# Moter_Control_2021-08-13.net
KiCad netlist of a schematic drawn in Altium Designer
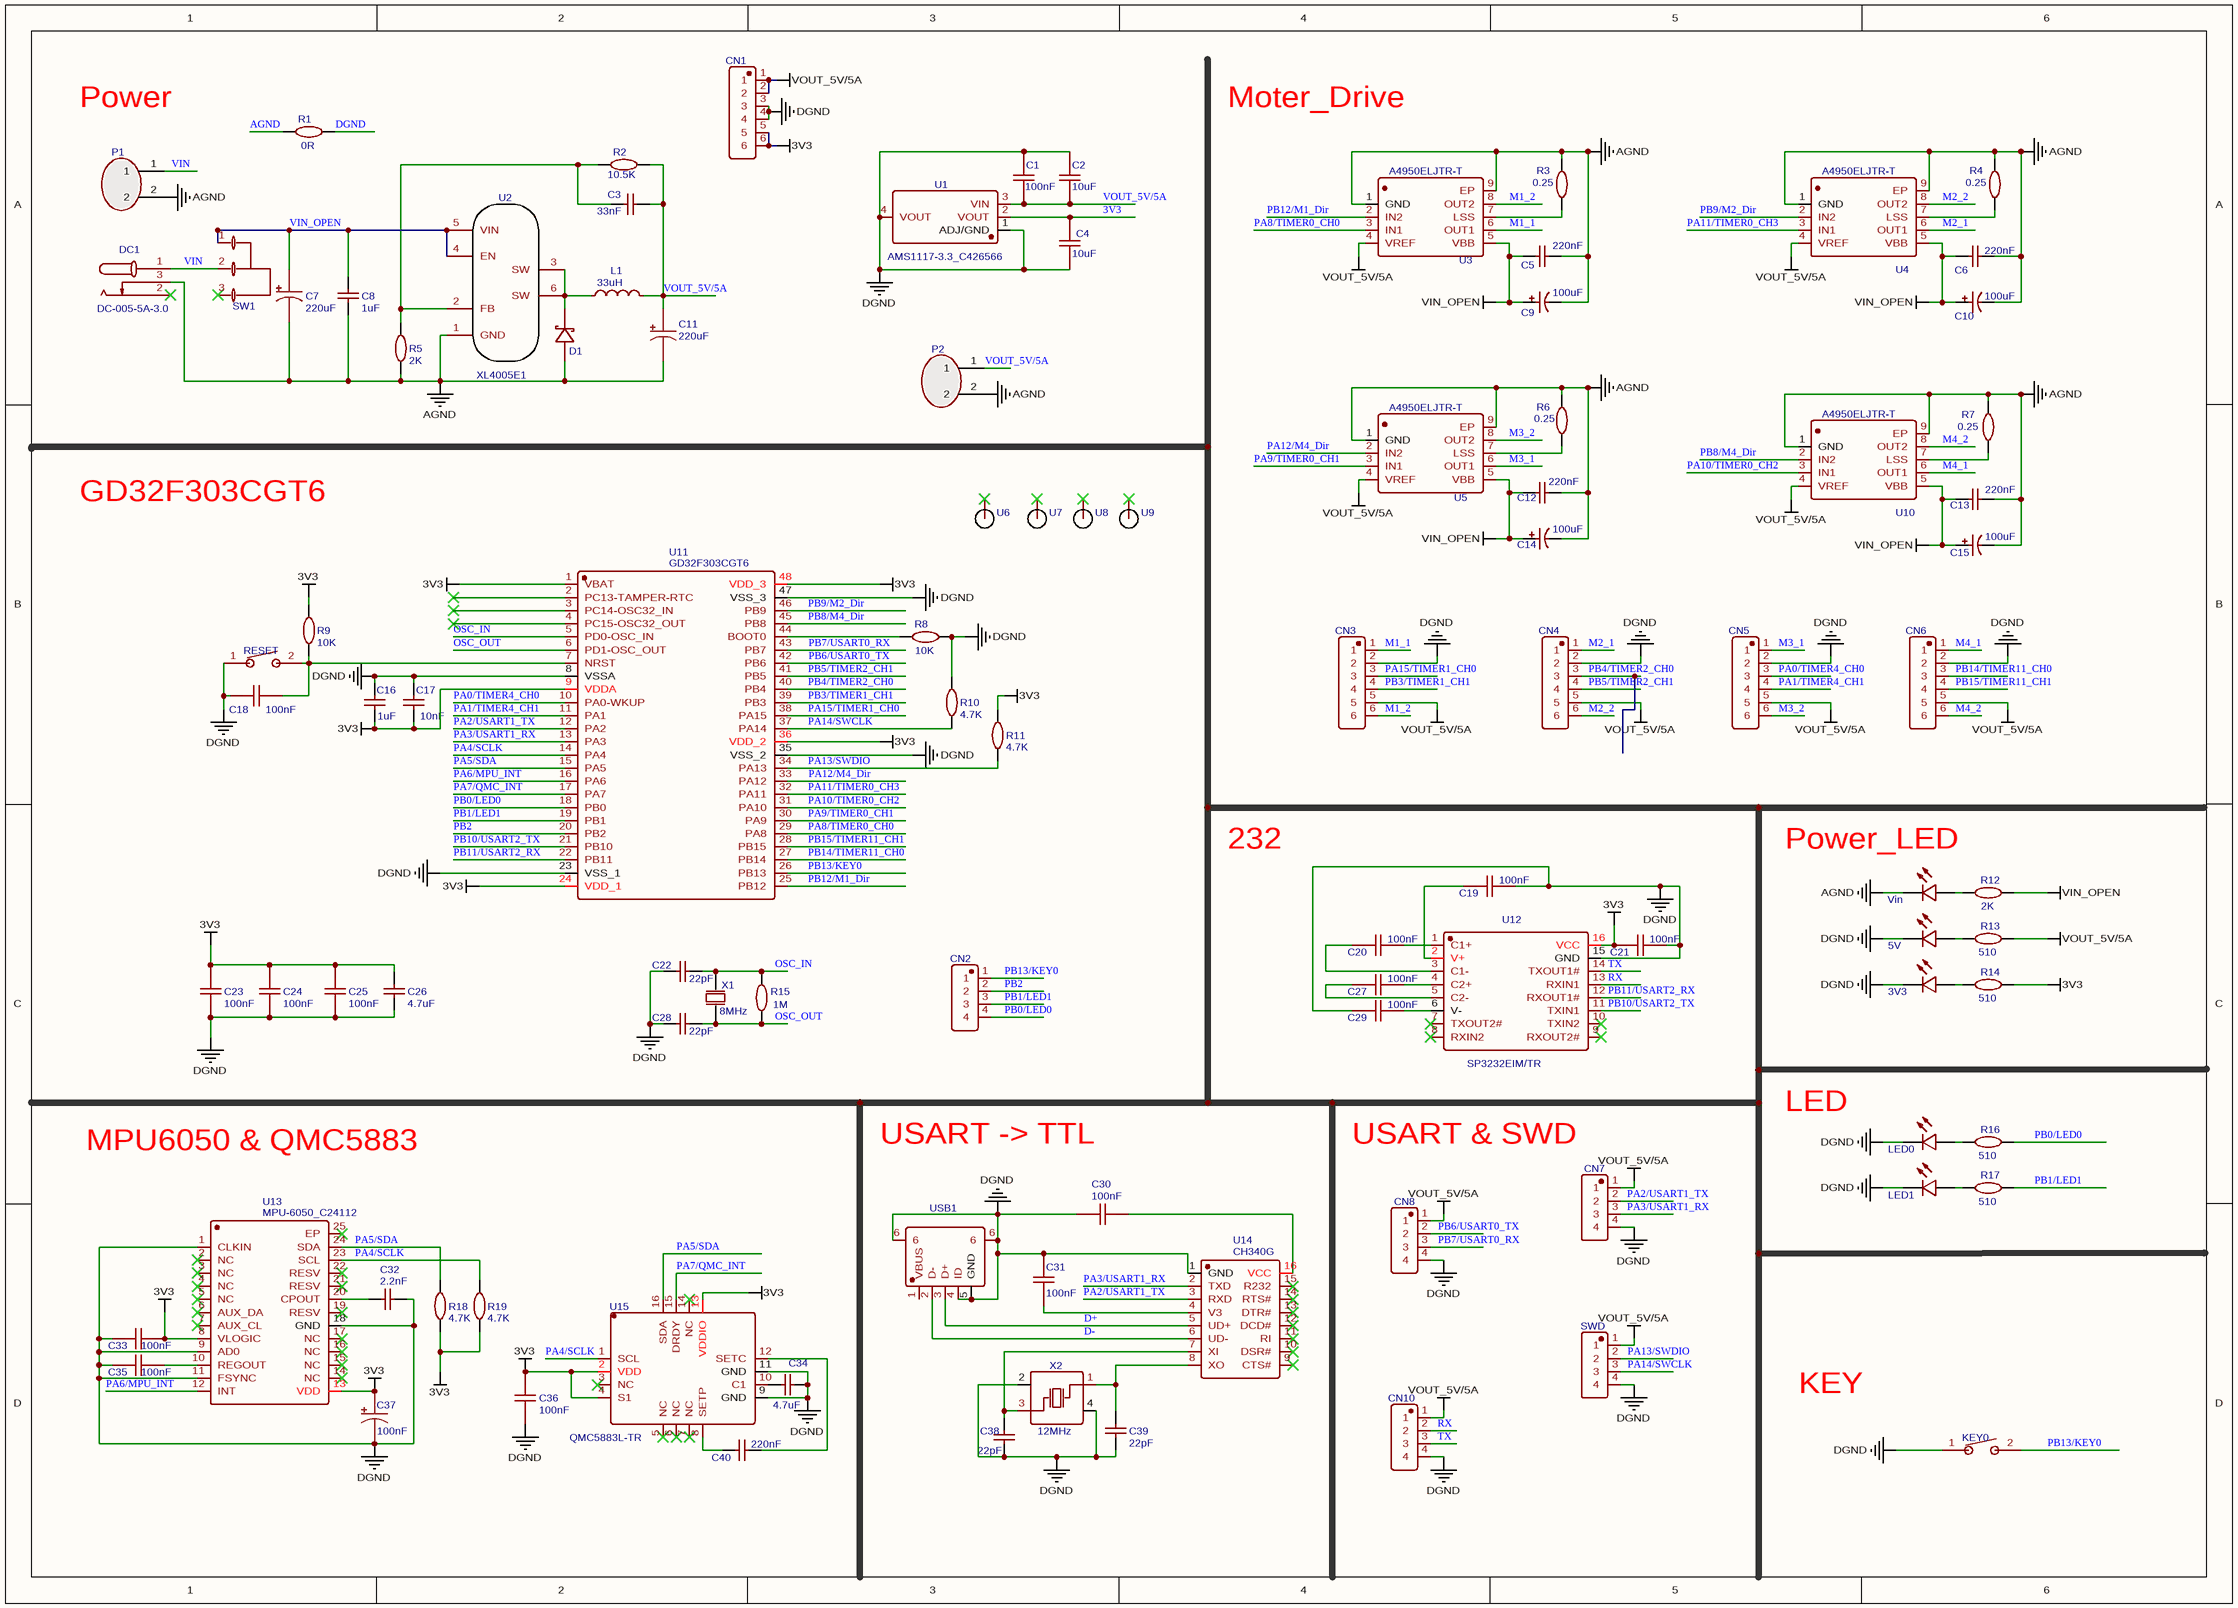
[diagram p0: Moter_Control_2021-08-13.schdoc]

(export (version "E")
  (design (tool "Eeschema 10.0.6"))
  (components
    (comp (ref "3V3")
      (value "19-217/BHC-ZL1M2RY/3T")
      (footprint "LED0603_B")
      (fields (field (name "BOM_SUPPLIER PART") "C72041"))
      (libsource (lib "altium-import") (part "root_0_19-217/BHC-ZL1M2RY/3T_"))
    )
    (comp (ref "5V")
      (value "19-217/BHC-ZL1M2RY/3T")
      (footprint "LED0603_B")
      (fields (field (name "BOM_SUPPLIER PART") "C72041"))
      (libsource (lib "altium-import") (part "root_0_19-217/BHC-ZL1M2RY/3T_"))
    )
    (comp (ref "C1")
      (value "100nF")
      (footprint "C0603_L")
      (fields
        (field (name "BOM_MANUFACTURER PART") "CC0603KRX7R9BB104")
        (field (name "BOM_SUPPLIER PART") "C14663")
      )
      (libsource (lib "altium-import") (part "root_1_100nF_"))
    )
    (comp (ref "C2")
      (value "10uF")
      (footprint "C0603_L")
      (fields
        (field (name "BOM_MANUFACTURER PART") "CL10A106MA8NRNC")
        (field (name "BOM_SUPPLIER PART") "C96446")
      )
      (libsource (lib "altium-import") (part "root_1_10uF_"))
    )
    (comp (ref "C3")
      (value "33nF")
      (footprint "C0603_L")
      (fields
        (field (name "BOM_MANUFACTURER PART") "CL10B333KB8NNNC")
        (field (name "BOM_SUPPLIER PART") "C21117")
      )
      (libsource (lib "altium-import") (part "root_0_33nF_"))
    )
    (comp (ref "C4")
      (value "10uF")
      (footprint "C0603_L")
      (fields
        (field (name "BOM_MANUFACTURER PART") "CL10A106MA8NRNC")
        (field (name "BOM_SUPPLIER PART") "C96446")
      )
      (libsource (lib "altium-import") (part "root_1_10uF_"))
    )
    (comp (ref "C5")
      (value "220nF")
      (footprint "C0603_L")
      (fields
        (field (name "BOM_MANUFACTURER PART") "CL10B224KA8NNNC")
        (field (name "BOM_SUPPLIER PART") "C21120")
      )
      (libsource (lib "altium-import") (part "root_2_220nF_"))
    )
    (comp (ref "C6")
      (value "220nF")
      (footprint "C0603_L")
      (fields
        (field (name "BOM_MANUFACTURER PART") "CL10B224KA8NNNC")
        (field (name "BOM_SUPPLIER PART") "C21120")
      )
      (libsource (lib "altium-import") (part "root_2_220nF_"))
    )
    (comp (ref "C7")
      (value "220uF")
      (footprint "CE E(8*10.2)")
      (fields
        (field (name "BOM_MANUFACTURER PART") "RVT1H471M1213")
        (field (name "BOM_SUPPLIER PART") "C90272")
      )
      (libsource (lib "altium-import") (part "root_0_470uF_"))
    )
    (comp (ref "C8")
      (value "1uF")
      (footprint "C0603_L")
      (fields
        (field (name "BOM_MANUFACTURER PART") "CL10A105KB8NNNC")
        (field (name "BOM_SUPPLIER PART") "C15849")
      )
      (libsource (lib "altium-import") (part "root_3_1uF_"))
    )
    (comp (ref "C9")
      (value "100uF")
      (footprint "CE D(6.3*7.7)")
      (fields
        (field (name "BOM_MANUFACTURER PART") "RVT1H101M0810")
        (field (name "BOM_SUPPLIER PART") "C3352")
      )
      (libsource (lib "altium-import") (part "root_0_100uF_"))
    )
    (comp (ref "C10")
      (value "100uF")
      (footprint "CE D(6.3*7.7)")
      (fields
        (field (name "BOM_MANUFACTURER PART") "RVT1H101M0810")
        (field (name "BOM_SUPPLIER PART") "C3352")
      )
      (libsource (lib "altium-import") (part "root_0_100uF_"))
    )
    (comp (ref "C11")
      (value "220uF")
      (footprint "CE E(8*10.2)")
      (fields
        (field (name "BOM_MANUFACTURER PART") "RVT1H471M1213")
        (field (name "BOM_SUPPLIER PART") "C90272")
      )
      (libsource (lib "altium-import") (part "root_0_470uF_"))
    )
    (comp (ref "C12")
      (value "220nF")
      (footprint "C0603_L")
      (fields
        (field (name "BOM_MANUFACTURER PART") "CL10B224KA8NNNC")
        (field (name "BOM_SUPPLIER PART") "C21120")
      )
      (libsource (lib "altium-import") (part "root_2_220nF_"))
    )
    (comp (ref "C13")
      (value "220nF")
      (footprint "C0603_L")
      (fields
        (field (name "BOM_MANUFACTURER PART") "CL10B224KA8NNNC")
        (field (name "BOM_SUPPLIER PART") "C21120")
      )
      (libsource (lib "altium-import") (part "root_2_220nF_"))
    )
    (comp (ref "C14")
      (value "100uF")
      (footprint "CE D(6.3*7.7)")
      (fields
        (field (name "BOM_MANUFACTURER PART") "RVT1H101M0810")
        (field (name "BOM_SUPPLIER PART") "C3352")
      )
      (libsource (lib "altium-import") (part "root_0_100uF_"))
    )
    (comp (ref "C15")
      (value "100uF")
      (footprint "CE D(6.3*7.7)")
      (fields
        (field (name "BOM_MANUFACTURER PART") "RVT1H101M0810")
        (field (name "BOM_SUPPLIER PART") "C3352")
      )
      (libsource (lib "altium-import") (part "root_0_100uF_"))
    )
    (comp (ref "C16")
      (value "1uF")
      (footprint "C0603_L")
      (fields
        (field (name "BOM_MANUFACTURER PART") "CL10A105KB8NNNC")
        (field (name "BOM_SUPPLIER PART") "C15849")
      )
      (libsource (lib "altium-import") (part "root_1_1uF_"))
    )
    (comp (ref "C17")
      (value "10nF")
      (footprint "C0603_L")
      (fields
        (field (name "BOM_MANUFACTURER PART") "0603B103K500NT")
        (field (name "BOM_SUPPLIER PART") "C57112")
      )
      (libsource (lib "altium-import") (part "root_1_10nF_"))
    )
    (comp (ref "C18")
      (value "100nF")
      (footprint "C0603_L")
      (fields
        (field (name "BOM_MANUFACTURER PART") "CC0603KRX7R9BB104")
        (field (name "BOM_SUPPLIER PART") "C14663")
      )
      (libsource (lib "altium-import") (part "root_0_100nF_"))
    )
    (comp (ref "C19")
      (value "100nF")
      (footprint "C0603_L")
      (fields
        (field (name "BOM_MANUFACTURER PART") "CC0603KRX7R9BB104")
        (field (name "BOM_SUPPLIER PART") "C14663")
      )
      (libsource (lib "altium-import") (part "root_2_100nF_"))
    )
    (comp (ref "C20")
      (value "100nF")
      (footprint "C0603_L")
      (fields
        (field (name "BOM_MANUFACTURER PART") "CC0603KRX7R9BB104")
        (field (name "BOM_SUPPLIER PART") "C14663")
      )
      (libsource (lib "altium-import") (part "root_2_100nF_"))
    )
    (comp (ref "C21")
      (value "100nF")
      (footprint "C0603_L")
      (fields
        (field (name "BOM_MANUFACTURER PART") "CC0603KRX7R9BB104")
        (field (name "BOM_SUPPLIER PART") "C14663")
      )
      (libsource (lib "altium-import") (part "root_2_100nF_"))
    )
    (comp (ref "C22")
      (value "22pF")
      (footprint "C0603_L")
      (fields
        (field (name "BOM_MANUFACTURER PART") "CL10C220JB8NNNC")
        (field (name "BOM_SUPPLIER PART") "C1653")
      )
      (libsource (lib "altium-import") (part "root_0_22pF_"))
    )
    (comp (ref "C23")
      (value "100nF")
      (footprint "C0603_L")
      (fields
        (field (name "BOM_MANUFACTURER PART") "CC0603KRX7R9BB104")
        (field (name "BOM_SUPPLIER PART") "C14663")
      )
      (libsource (lib "altium-import") (part "root_1_100nF_"))
    )
    (comp (ref "C24")
      (value "100nF")
      (footprint "C0603_L")
      (fields
        (field (name "BOM_MANUFACTURER PART") "CC0603KRX7R9BB104")
        (field (name "BOM_SUPPLIER PART") "C14663")
      )
      (libsource (lib "altium-import") (part "root_1_100nF_"))
    )
    (comp (ref "C25")
      (value "100nF")
      (footprint "C0603_L")
      (fields
        (field (name "BOM_MANUFACTURER PART") "CC0603KRX7R9BB104")
        (field (name "BOM_SUPPLIER PART") "C14663")
      )
      (libsource (lib "altium-import") (part "root_1_100nF_"))
    )
    (comp (ref "C26")
      (value "4.7uF")
      (footprint "C0603_L")
      (fields
        (field (name "BOM_MANUFACTURER PART") "CL10A475KO8NNNC")
        (field (name "BOM_SUPPLIER PART") "C19666")
      )
      (libsource (lib "altium-import") (part "root_1_4.7uF_"))
    )
    (comp (ref "C27")
      (value "100nF")
      (footprint "C0603_L")
      (fields
        (field (name "BOM_MANUFACTURER PART") "CC0603KRX7R9BB104")
        (field (name "BOM_SUPPLIER PART") "C14663")
      )
      (libsource (lib "altium-import") (part "root_2_100nF_"))
    )
    (comp (ref "C28")
      (value "22pF")
      (footprint "C0603_L")
      (fields
        (field (name "BOM_MANUFACTURER PART") "CL10C220JB8NNNC")
        (field (name "BOM_SUPPLIER PART") "C1653")
      )
      (libsource (lib "altium-import") (part "root_0_22pF_"))
    )
    (comp (ref "C29")
      (value "100nF")
      (footprint "C0603_L")
      (fields
        (field (name "BOM_MANUFACTURER PART") "CC0603KRX7R9BB104")
        (field (name "BOM_SUPPLIER PART") "C14663")
      )
      (libsource (lib "altium-import") (part "root_2_100nF_"))
    )
    (comp (ref "C30")
      (value "100nF")
      (footprint "C0603_L")
      (fields
        (field (name "BOM_MANUFACTURER PART") "CC0603KRX7R9BB104")
        (field (name "BOM_SUPPLIER PART") "C14663")
      )
      (libsource (lib "altium-import") (part "root_2_100nF_"))
    )
    (comp (ref "C31")
      (value "100nF")
      (footprint "C0603_L")
      (fields
        (field (name "BOM_MANUFACTURER PART") "CC0603KRX7R9BB104")
        (field (name "BOM_SUPPLIER PART") "C14663")
      )
      (libsource (lib "altium-import") (part "root_1_100nF_"))
    )
    (comp (ref "C32")
      (value "2.2nF")
      (footprint "C0603_L")
      (fields
        (field (name "BOM_MANUFACTURER PART") "0603B222K500NT")
        (field (name "BOM_SUPPLIER PART") "C1604")
      )
      (libsource (lib "altium-import") (part "root_0_2.2nF_"))
    )
    (comp (ref "C33")
      (value "100nF")
      (footprint "C0603_L")
      (fields
        (field (name "BOM_MANUFACTURER PART") "CC0603KRX7R9BB104")
        (field (name "BOM_SUPPLIER PART") "C14663")
      )
      (libsource (lib "altium-import") (part "root_0_100nF_"))
    )
    (comp (ref "C34")
      (value "4.7uF")
      (footprint "C0603_L")
      (fields
        (field (name "BOM_MANUFACTURER PART") "CL10A475KO8NNNC")
        (field (name "BOM_SUPPLIER PART") "C19666")
      )
      (libsource (lib "altium-import") (part "root_0_4.7uF_"))
    )
    (comp (ref "C35")
      (value "100nF")
      (footprint "C0603_L")
      (fields
        (field (name "BOM_MANUFACTURER PART") "CC0603KRX7R9BB104")
        (field (name "BOM_SUPPLIER PART") "C14663")
      )
      (libsource (lib "altium-import") (part "root_0_100nF_"))
    )
    (comp (ref "C36")
      (value "100nF")
      (footprint "C0603_L")
      (fields
        (field (name "BOM_MANUFACTURER PART") "CC0603KRX7R9BB104")
        (field (name "BOM_SUPPLIER PART") "C14663")
      )
      (libsource (lib "altium-import") (part "root_1_100nF_"))
    )
    (comp (ref "C37")
      (value "100nF")
      (footprint "CAP-SMD_L3.2-W1.6-R-RD")
      (fields
        (field (name "BOM_MANUFACTURER PART") "T491A104K035AT")
        (field (name "BOM_SUPPLIER PART") "C122257")
        (field (name "CONTRIBUTOR") "LCSC")
      )
      (libsource (lib "") (part "root_1_100nF__1"))
    )
    (comp (ref "C38")
      (value "22pF")
      (footprint "C0603_L")
      (fields
        (field (name "BOM_MANUFACTURER PART") "CL10C220JB8NNNC")
        (field (name "BOM_SUPPLIER PART") "C1653")
      )
      (libsource (lib "altium-import") (part "root_1_22pF_"))
    )
    (comp (ref "C39")
      (value "22pF")
      (footprint "C0603_L")
      (fields
        (field (name "BOM_MANUFACTURER PART") "CL10C220JB8NNNC")
        (field (name "BOM_SUPPLIER PART") "C1653")
      )
      (libsource (lib "altium-import") (part "root_3_22pF_"))
    )
    (comp (ref "C40")
      (value "220nF")
      (footprint "C0603_L")
      (fields
        (field (name "BOM_MANUFACTURER PART") "CL10B224KA8NNNC")
        (field (name "BOM_SUPPLIER PART") "C21120")
      )
      (libsource (lib "altium-import") (part "root_0_220nF_"))
    )
    (comp (ref "CN1")
      (value "HX25003-6WAP")
      (footprint "Test_2.54_2×3Pin")
      (fields (field (name "BOM_SUPPLIER PART") "C442330") (field (name "CONTRIBUTOR") "LCSC"))
      (libsource (lib "altium-import") (part "root_0_HX25003-6WAP_"))
    )
    (comp (ref "CN2")
      (value "GP26-2520WV-4P")
      (footprint "Test_2.54_4Pin")
      (fields (field (name "BOM_SUPPLIER PART") "C2681739") (field (name "CONTRIBUTOR") "LCSC"))
      (libsource (lib "altium-import") (part "root_0_GP26-2520WV-4P_"))
    )
    (comp (ref "CN3")
      (value "HX25003-6WAP")
      (footprint "XH2.54-WI-6P")
      (fields (field (name "BOM_SUPPLIER PART") "C442330") (field (name "CONTRIBUTOR") "LCSC"))
      (libsource (lib "altium-import") (part "root_0_HX25003-6WAP_"))
    )
    (comp (ref "CN4")
      (value "HX25003-6WAP")
      (footprint "XH2.54-WI-6P")
      (fields (field (name "BOM_SUPPLIER PART") "C442330") (field (name "CONTRIBUTOR") "LCSC"))
      (libsource (lib "altium-import") (part "root_0_HX25003-6WAP_"))
    )
    (comp (ref "CN5")
      (value "HX25003-6WAP")
      (footprint "XH2.54-WI-6P")
      (fields (field (name "BOM_SUPPLIER PART") "C442330") (field (name "CONTRIBUTOR") "LCSC"))
      (libsource (lib "altium-import") (part "root_0_HX25003-6WAP_"))
    )
    (comp (ref "CN6")
      (value "HX25003-6WAP")
      (footprint "XH2.54-WI-6P")
      (fields (field (name "BOM_SUPPLIER PART") "C442330") (field (name "CONTRIBUTOR") "LCSC"))
      (libsource (lib "altium-import") (part "root_0_HX25003-6WAP_"))
    )
    (comp (ref "CN7")
      (value "HX25035-4WAP")
      (footprint "Test_2.54_4Pin")
      (fields (field (name "BOM_SUPPLIER PART") "C442385") (field (name "CONTRIBUTOR") "LCSC"))
      (libsource (lib "altium-import") (part "root_0_HX25035-4WAP_"))
    )
    (comp (ref "CN8")
      (value "HX25035-4WAP")
      (footprint "XH2.54-WI-4P")
      (fields (field (name "BOM_SUPPLIER PART") "C442385") (field (name "CONTRIBUTOR") "LCSC"))
      (libsource (lib "altium-import") (part "root_0_HX25035-4WAP_"))
    )
    (comp (ref "CN10")
      (value "HX25035-4WAP")
      (footprint "XH2.54-WI-4P")
      (fields (field (name "BOM_SUPPLIER PART") "C442385") (field (name "CONTRIBUTOR") "LCSC"))
      (libsource (lib "altium-import") (part "root_0_HX25035-4WAP_"))
    )
    (comp (ref "D1")
      (value "SS54_C727065")
      (footprint "SMA_L4.3-W2.6-LS5.0-RD")
      (fields
        (field (name "BOM_SUPPLIER PART") "C727065")
        (field (name "BOM_MANUFACTURER PART") "SS54")
        (field (name "CONTRIBUTOR") "LCSC")
      )
      (libsource (lib "altium-import") (part "root_3_SS54_C727065_"))
    )
    (comp (ref "DC1")
      (value "DC-005-5A-3.0")
      (footprint "DC-IN-TH_DC-005-5A-3.0")
      (fields (field (name "BOM_SUPPLIER PART") "C388625") (field (name "CONTRIBUTOR") "LCSC"))
      (libsource (lib "altium-import") (part "root_0_DC-005-5A-3.0_"))
    )
    (comp (ref "KEY0")
      (value "TSA363G25-250B")
      (footprint "SW-SMD_L6.5-W3.6-LS8.0")
      (fields (field (name "BOM_SUPPLIER PART") "C354943") (field (name "CONTRIBUTOR") "LCSC"))
      (libsource (lib "altium-import") (part "root_0_TSA363G25-250B_"))
    )
    (comp (ref "L1")
      (value "33uH")
      (footprint "IND-SMD_L13.45-W12.6")
      (fields
        (field (name "BOM_SUPPLIER PART") "C408530")
        (field (name "BOM_MANUFACTURER PART") "MWSA1206S-330MT")
        (field (name "CONTRIBUTOR") "LCSC")
      )
      (libsource (lib "altium-import") (part "root_0_33uH_"))
    )
    (comp (ref "LED0")
      (value "19-217/BHC-ZL1M2RY/3T")
      (footprint "LED0603_B")
      (fields (field (name "BOM_SUPPLIER PART") "C72041"))
      (libsource (lib "altium-import") (part "root_0_19-217/BHC-ZL1M2RY/3T_"))
    )
    (comp (ref "LED1")
      (value "19-217/BHC-ZL1M2RY/3T")
      (footprint "LED0603_B")
      (fields (field (name "BOM_SUPPLIER PART") "C72041"))
      (libsource (lib "altium-import") (part "root_0_19-217/BHC-ZL1M2RY/3T_"))
    )
    (comp (ref "P1")
      (value "WJ126V-5.0-2P")
      (footprint "HT3.96-WI-2P-ORG")
      (fields (field (name "BOM_SUPPLIER PART") "C8404"))
      (libsource (lib "altium-import") (part "root_0_WJ126V-5.0-2P_"))
    )
    (comp (ref "P2")
      (value "WJ126V-5.0-2P")
      (footprint "HT3.96-WI-2P-ORG")
      (fields (field (name "BOM_SUPPLIER PART") "C8404"))
      (libsource (lib "altium-import") (part "root_0_WJ126V-5.0-2P_"))
    )
    (comp (ref "R1")
      (value "0R")
      (footprint "R0805_L")
      (fields
        (field (name "BOM_MANUFACTURER PART") "0603WAF0000T5E")
        (field (name "BOM_SUPPLIER PART") "C21189")
      )
      (libsource (lib "altium-import") (part "root_0_0R_"))
    )
    (comp (ref "R2")
      (value "10.5K")
      (footprint "R0603_L")
      (fields
        (field (name "BOM_MANUFACTURER PART") "0603WAF1052T5E")
        (field (name "BOM_SUPPLIER PART") "C22855")
      )
      (libsource (lib "altium-import") (part "root_2_10.5K_"))
    )
    (comp (ref "R3")
      (value "0.25")
      (footprint "R2512_L")
      (fields
        (field (name "BOM_MANUFACTURER PART") "25121WF250LT4E")
        (field (name "BOM_SUPPLIER PART") "C25467")
      )
      (libsource (lib "altium-import") (part "root_3_0.25_"))
    )
    (comp (ref "R4")
      (value "0.25")
      (footprint "R2512_L")
      (fields
        (field (name "BOM_MANUFACTURER PART") "25121WF250LT4E")
        (field (name "BOM_SUPPLIER PART") "C25467")
      )
      (libsource (lib "altium-import") (part "root_3_0.25_"))
    )
    (comp (ref "R5")
      (value "2K")
      (footprint "R0603_L")
      (fields
        (field (name "BOM_MANUFACTURER PART") "0603WAF2001T5E")
        (field (name "BOM_SUPPLIER PART") "C22975")
      )
      (libsource (lib "altium-import") (part "root_1_2K_"))
    )
    (comp (ref "R6")
      (value "0.25")
      (footprint "R2512_L")
      (fields
        (field (name "BOM_MANUFACTURER PART") "25121WF250LT4E")
        (field (name "BOM_SUPPLIER PART") "C25467")
      )
      (libsource (lib "altium-import") (part "root_3_0.25_"))
    )
    (comp (ref "R7")
      (value "0.25")
      (footprint "R2512_L")
      (fields
        (field (name "BOM_MANUFACTURER PART") "25121WF250LT4E")
        (field (name "BOM_SUPPLIER PART") "C25467")
      )
      (libsource (lib "altium-import") (part "root_3_0.25_"))
    )
    (comp (ref "R8")
      (value "10K")
      (footprint "R0603_L")
      (fields
        (field (name "BOM_MANUFACTURER PART") "0603WAF1002T5E")
        (field (name "BOM_SUPPLIER PART") "C25804")
      )
      (libsource (lib "altium-import") (part "root_0_10K_"))
    )
    (comp (ref "R9")
      (value "10K")
      (footprint "R0603_L")
      (fields
        (field (name "BOM_MANUFACTURER PART") "0603WAF1002T5E")
        (field (name "BOM_SUPPLIER PART") "C25804")
      )
      (libsource (lib "altium-import") (part "root_1_10K_"))
    )
    (comp (ref "R10")
      (value "4.7K")
      (footprint "R0603_L")
      (fields
        (field (name "BOM_MANUFACTURER PART") "RC0603FR-074K7L")
        (field (name "BOM_SUPPLIER PART") "C99782")
      )
      (libsource (lib "altium-import") (part "root_1_4.7K_"))
    )
    (comp (ref "R11")
      (value "4.7K")
      (footprint "R0603_L")
      (fields
        (field (name "BOM_MANUFACTURER PART") "RC0603FR-074K7L")
        (field (name "BOM_SUPPLIER PART") "C99782")
      )
      (libsource (lib "altium-import") (part "root_1_4.7K_"))
    )
    (comp (ref "R12")
      (value "2K")
      (footprint "R0603_L")
      (fields
        (field (name "BOM_MANUFACTURER PART") "0603WAF2001T5E")
        (field (name "BOM_SUPPLIER PART") "C22975")
      )
      (libsource (lib "altium-import") (part "root_0_2K_"))
    )
    (comp (ref "R13")
      (value "510")
      (footprint "R0603_L")
      (fields
        (field (name "BOM_MANUFACTURER PART") "0603WAF5100T5E")
        (field (name "BOM_SUPPLIER PART") "C23193")
      )
      (libsource (lib "altium-import") (part "root_0_510_"))
    )
    (comp (ref "R14")
      (value "510")
      (footprint "R0603_L")
      (fields
        (field (name "BOM_MANUFACTURER PART") "0603WAF5100T5E")
        (field (name "BOM_SUPPLIER PART") "C23193")
      )
      (libsource (lib "altium-import") (part "root_0_510_"))
    )
    (comp (ref "R15")
      (value "1M")
      (footprint "R0603_L")
      (fields
        (field (name "BOM_MANUFACTURER PART") "0603WAF1004T5E")
        (field (name "BOM_SUPPLIER PART") "C22935")
      )
      (libsource (lib "altium-import") (part "root_1_1M_"))
    )
    (comp (ref "R16")
      (value "510")
      (footprint "R0603_L")
      (fields
        (field (name "BOM_MANUFACTURER PART") "0603WAF5100T5E")
        (field (name "BOM_SUPPLIER PART") "C23193")
      )
      (libsource (lib "altium-import") (part "root_0_510_"))
    )
    (comp (ref "R17")
      (value "510")
      (footprint "R0603_L")
      (fields
        (field (name "BOM_MANUFACTURER PART") "0603WAF5100T5E")
        (field (name "BOM_SUPPLIER PART") "C23193")
      )
      (libsource (lib "altium-import") (part "root_0_510_"))
    )
    (comp (ref "R18")
      (value "4.7K")
      (footprint "R0603_L")
      (fields
        (field (name "BOM_MANUFACTURER PART") "0603WAF4701T5E")
        (field (name "BOM_SUPPLIER PART") "C23162")
      )
      (libsource (lib "altium-import") (part "root_1_4.7K_"))
    )
    (comp (ref "R19")
      (value "4.7K")
      (footprint "R0603_L")
      (fields
        (field (name "BOM_MANUFACTURER PART") "0603WAF4701T5E")
        (field (name "BOM_SUPPLIER PART") "C23162")
      )
      (libsource (lib "altium-import") (part "root_1_4.7K_"))
    )
    (comp (ref "RESET")
      (value "TSA363G25-250B")
      (footprint "SW-SMD_L6.5-W3.6-LS8.0")
      (fields (field (name "BOM_SUPPLIER PART") "C354943") (field (name "CONTRIBUTOR") "LCSC"))
      (libsource (lib "altium-import") (part "root_0_TSA363G25-250B_"))
    )
    (comp (ref "SW1")
      (value "SS-12D06L5")
      (footprint "SS-12D10")
      (fields (field (name "BOM_SUPPLIER PART") "C319015") (field (name "CONTRIBUTOR") "LCSC"))
      (libsource (lib "altium-import") (part "root_3_mirrored_SS-12D06L5_"))
    )
    (comp (ref "SWD")
      (value "HX25035-4WAP")
      (footprint "Test_2.54_4Pin")
      (fields (field (name "BOM_SUPPLIER PART") "C442385") (field (name "CONTRIBUTOR") "LCSC"))
      (libsource (lib "altium-import") (part "root_0_HX25035-4WAP_"))
    )
    (comp (ref "U1")
      (value "AMS1117-3.3_C426566")
      (footprint "SOT-223_L6.5-W3.5-P2.30-LS7.0-BR")
      (fields
        (field (name "BOM_SUPPLIER PART") "C426566")
        (field (name "BOM_MANUFACTURER PART") "AMS1117-3.3")
        (field (name "CONTRIBUTOR") "LCSC")
      )
      (libsource (lib "altium-import") (part "root_2_AMS1117-3.3_C426566_"))
    )
    (comp (ref "U2")
      (value "XL4005E1")
      (footprint "TO-263-5_L10.2-W9.2-P1.70-TL")
      (fields (field (name "BOM_SUPPLIER PART") "C73332"))
      (libsource (lib "altium-import") (part "root_0_XL4005E1_"))
    )
    (comp (ref "U3")
      (value "A4950ELJTR-T")
      (footprint "A4950")
      (fields (field (name "BOM_SUPPLIER PART") "C82404"))
      (libsource (lib "altium-import") (part "root_0_A4950ELJTR-T_"))
    )
    (comp (ref "U4")
      (value "A4950ELJTR-T")
      (footprint "A4950")
      (fields (field (name "BOM_SUPPLIER PART") "C82404"))
      (libsource (lib "altium-import") (part "root_0_A4950ELJTR-T_"))
    )
    (comp (ref "U5")
      (value "A4950ELJTR-T")
      (footprint "A4950")
      (fields (field (name "BOM_SUPPLIER PART") "C82404"))
      (libsource (lib "altium-import") (part "root_0_A4950ELJTR-T_"))
    )
    (comp (ref "U6")
      (value "Fix")
      (footprint "FIX")
      (fields (field (name "CONTRIBUTOR") "xdyewu"))
      (libsource (lib "altium-import") (part "root_0_Fix_"))
    )
    (comp (ref "U7")
      (value "Fix")
      (footprint "FIX")
      (fields (field (name "CONTRIBUTOR") "xdyewu"))
      (libsource (lib "altium-import") (part "root_0_Fix_"))
    )
    (comp (ref "U8")
      (value "Fix")
      (footprint "FIX")
      (fields (field (name "CONTRIBUTOR") "xdyewu"))
      (libsource (lib "altium-import") (part "root_0_Fix_"))
    )
    (comp (ref "U9")
      (value "Fix")
      (footprint "FIX")
      (fields (field (name "CONTRIBUTOR") "xdyewu"))
      (libsource (lib "altium-import") (part "root_0_Fix_"))
    )
    (comp (ref "U10")
      (value "A4950ELJTR-T")
      (footprint "A4950")
      (fields (field (name "BOM_SUPPLIER PART") "C82404"))
      (libsource (lib "altium-import") (part "root_0_A4950ELJTR-T_"))
    )
    (comp (ref "U11")
      (value "GD32F303CGT6")
      (footprint "Moter_Control_2021-08-13:LQFP-48_L7.0-W7.0-P0.50-LS9.0-BL")
      (fields (field (name "BOM_SUPPLIER PART") "C2835084") (field (name "CONTRIBUTOR") "LCSC"))
      (libsource (lib "altium-import") (part "root_0_GD32F303CGT6_"))
    )
    (comp (ref "U12")
      (value "SP3232EIM/TR")
      (footprint "SOP-16_L10.0-W3.9-P1.27-LS6.0-BL")
      (fields (field (name "BOM_SUPPLIER PART") "C519088") (field (name "CONTRIBUTOR") "LCSC"))
      (libsource (lib "altium-import") (part "root_0_SP3232EIM/TR_"))
    )
    (comp (ref "U13")
      (value "MPU-6050_C24112")
      (footprint "QFN-24_L4.0-W4.0-P0.50-BL-EP2.6")
      (fields (field (name "BOM_MANUFACTURER PART") "MPU-6050") (field (name "BOM_SUPPLIER PART") "C24112"))
      (libsource (lib "altium-import") (part "root_0_MPU-6050_C24112_"))
    )
    (comp (ref "U14")
      (value "CH340G")
      (footprint "SOIC-16_L9.9-W3.9-P1.27-LS6.0-BR")
      (fields (field (name "BOM_SUPPLIER PART") "C14267"))
      (libsource (lib "altium-import") (part "root_0_CH340G_"))
    )
    (comp (ref "U15")
      (value "QMC5883L-TR")
      (footprint "SENSOR-SMD_QMC5883L-TR")
      (fields (field (name "BOM_SUPPLIER PART") "C192585") (field (name "CONTRIBUTOR") "LCSC"))
      (libsource (lib "altium-import") (part "root_0_QMC5883L-TR_"))
    )
    (comp (ref "USB1")
      (value "U-M-M5DS-W-5_C2689963")
      (footprint "USB-MICRO_D")
      (fields
        (field (name "BOM_SUPPLIER PART") "C2689963")
        (field (name "BOM_MANUFACTURER PART") "U-M-M5DS-W-5")
        (field (name "CONTRIBUTOR") "LCSC")
      )
      (libsource (lib "altium-import") (part "root_1_U-M-M5DS-W-5_C2689963_"))
    )
    (comp (ref "Vin")
      (value "19-217/BHC-ZL1M2RY/3T")
      (footprint "LED0603_B")
      (fields (field (name "BOM_SUPPLIER PART") "C72041"))
      (libsource (lib "altium-import") (part "root_0_19-217/BHC-ZL1M2RY/3T_"))
    )
    (comp (ref "X1")
      (value "8MHz")
      (footprint "OSC 5032-2P-Black")
      (fields
        (field (name "BOM_MANUFACTURER PART") "X50328MSB2GI")
        (field (name "BOM_SUPPLIER PART") "C115962")
      )
      (libsource (lib "altium-import") (part "root_1_8MHz_"))
    )
    (comp (ref "X2")
      (value "12MHz")
      (footprint "OSC 3225-4P")
      (fields
        (field (name "BOM_MANUFACTURER PART") "X322512MSB4SI")
        (field (name "BOM_SUPPLIER PART") "C9002")
      )
      (libsource (lib "altium-import") (part "root_2_12MHz_"))
    )
  )
  (nets
    (net (code "1") (name "/D+") (class "Default")
      (node (ref "U14") (pin "5") (pinfunction "UD+_5") (pintype "passive"))
      (node (ref "USB1") (pin "3") (pinfunction "D+_3") (pintype "passive"))
    )
    (net (code "2") (name "/D-") (class "Default")
      (node (ref "U14") (pin "6") (pinfunction "UD-_6") (pintype "passive"))
      (node (ref "USB1") (pin "2") (pinfunction "D-_2") (pintype "passive"))
    )
    (net (code "3") (name "/M1_1") (class "Default")
      (node (ref "CN3") (pin "1") (pinfunction "1_1") (pintype "passive"))
      (node (ref "U3") (pin "6") (pinfunction "OUT1_6") (pintype "passive"))
    )
    (net (code "4") (name "/M1_2") (class "Default")
      (node (ref "CN3") (pin "6") (pinfunction "6_6") (pintype "passive"))
      (node (ref "U3") (pin "8") (pinfunction "OUT2_8") (pintype "passive"))
    )
    (net (code "5") (name "/M2_1") (class "Default")
      (node (ref "CN4") (pin "1") (pinfunction "1_1") (pintype "passive"))
      (node (ref "U4") (pin "6") (pinfunction "OUT1_6") (pintype "passive"))
    )
    (net (code "6") (name "/M2_2") (class "Default")
      (node (ref "CN4") (pin "6") (pinfunction "6_6") (pintype "passive"))
      (node (ref "U4") (pin "8") (pinfunction "OUT2_8") (pintype "passive"))
    )
    (net (code "7") (name "/M3_1") (class "Default")
      (node (ref "CN5") (pin "1") (pinfunction "1_1") (pintype "passive"))
      (node (ref "U5") (pin "6") (pinfunction "OUT1_6") (pintype "passive"))
    )
    (net (code "8") (name "/M3_2") (class "Default")
      (node (ref "CN5") (pin "6") (pinfunction "6_6") (pintype "passive"))
      (node (ref "U5") (pin "8") (pinfunction "OUT2_8") (pintype "passive"))
    )
    (net (code "9") (name "/M4_1") (class "Default")
      (node (ref "CN6") (pin "1") (pinfunction "1_1") (pintype "passive"))
      (node (ref "U10") (pin "6") (pinfunction "OUT1_6") (pintype "passive"))
    )
    (net (code "10") (name "/M4_2") (class "Default")
      (node (ref "CN6") (pin "6") (pinfunction "6_6") (pintype "passive"))
      (node (ref "U10") (pin "8") (pinfunction "OUT2_8") (pintype "passive"))
    )
    (net (code "11") (name "/OSC_IN") (class "Default")
      (node (ref "C22") (pin "2") (pinfunction "2_2") (pintype "passive"))
      (node (ref "R15") (pin "2") (pinfunction "2_2") (pintype "passive"))
      (node (ref "U11") (pin "5") (pinfunction "PD0-OSC_IN_5") (pintype "passive"))
      (node (ref "X1") (pin "2") (pinfunction "OSC2_2") (pintype "passive"))
    )
    (net (code "12") (name "/OSC_OUT") (class "Default")
      (node (ref "C28") (pin "2") (pinfunction "2_2") (pintype "passive"))
      (node (ref "R15") (pin "1") (pinfunction "1_1") (pintype "passive"))
      (node (ref "U11") (pin "6") (pinfunction "PD1-OSC_OUT_6") (pintype "passive"))
      (node (ref "X1") (pin "1") (pinfunction "OSC1_1") (pintype "passive"))
    )
    (net (code "13") (name "/PA0{slash}TIMER4_CH0") (class "Default")
      (node (ref "CN5") (pin "3") (pinfunction "3_3") (pintype "passive"))
      (node (ref "U11") (pin "10") (pinfunction "PA0-WKUP_10") (pintype "passive"))
    )
    (net (code "14") (name "/PA1{slash}TIMER4_CH1") (class "Default")
      (node (ref "CN5") (pin "4") (pinfunction "4_4") (pintype "passive"))
      (node (ref "U11") (pin "11") (pinfunction "PA1_11") (pintype "passive"))
    )
    (net (code "15") (name "/PA2{slash}USART1_TX") (class "Default")
      (node (ref "CN7") (pin "2") (pinfunction "2_2") (pintype "passive"))
      (node (ref "U11") (pin "12") (pinfunction "PA2_12") (pintype "passive"))
      (node (ref "U14") (pin "3") (pinfunction "RXD_3") (pintype "passive"))
    )
    (net (code "16") (name "/PA3{slash}USART1_RX") (class "Default")
      (node (ref "CN7") (pin "3") (pinfunction "3_3") (pintype "passive"))
      (node (ref "U11") (pin "13") (pinfunction "PA3_13") (pintype "passive"))
      (node (ref "U14") (pin "2") (pinfunction "TXD_2") (pintype "passive"))
    )
    (net (code "17") (name "/PA4{slash}SCLK") (class "Default")
      (node (ref "R19") (pin "2") (pinfunction "2_2") (pintype "passive"))
      (node (ref "U11") (pin "14") (pinfunction "PA4_14") (pintype "passive"))
      (node (ref "U13") (pin "23") (pinfunction "SCL_23") (pintype "passive"))
      (node (ref "U15") (pin "1") (pinfunction "SCL_1") (pintype "passive"))
    )
    (net (code "18") (name "/PA5{slash}SDA") (class "Default")
      (node (ref "R18") (pin "2") (pinfunction "2_2") (pintype "passive"))
      (node (ref "U11") (pin "15") (pinfunction "PA5_15") (pintype "passive"))
      (node (ref "U13") (pin "24") (pinfunction "SDA_24") (pintype "passive"))
      (node (ref "U15") (pin "16") (pinfunction "SDA_16") (pintype "passive"))
    )
    (net (code "19") (name "/PA6{slash}MPU_INT") (class "Default")
      (node (ref "U11") (pin "16") (pinfunction "PA6_16") (pintype "passive"))
      (node (ref "U13") (pin "12") (pinfunction "INT_12") (pintype "passive"))
    )
    (net (code "20") (name "/PA7{slash}QMC_INT") (class "Default")
      (node (ref "U11") (pin "17") (pinfunction "PA7_17") (pintype "passive"))
      (node (ref "U15") (pin "15") (pinfunction "DRDY_15") (pintype "passive"))
    )
    (net (code "21") (name "/PA8{slash}TIMER0_CH0") (class "Default")
      (node (ref "U11") (pin "29") (pinfunction "PA8_29") (pintype "passive"))
      (node (ref "U3") (pin "3") (pinfunction "IN1_3") (pintype "passive"))
    )
    (net (code "22") (name "/PA9{slash}TIMER0_CH1") (class "Default")
      (node (ref "U11") (pin "30") (pinfunction "PA9_30") (pintype "passive"))
      (node (ref "U5") (pin "3") (pinfunction "IN1_3") (pintype "passive"))
    )
    (net (code "23") (name "/PA10{slash}TIMER0_CH2") (class "Default")
      (node (ref "U10") (pin "3") (pinfunction "IN1_3") (pintype "passive"))
      (node (ref "U11") (pin "31") (pinfunction "PA10_31") (pintype "passive"))
    )
    (net (code "24") (name "/PA11{slash}TIMER0_CH3") (class "Default")
      (node (ref "U11") (pin "32") (pinfunction "PA11_32") (pintype "passive"))
      (node (ref "U4") (pin "3") (pinfunction "IN1_3") (pintype "passive"))
    )
    (net (code "25") (name "/PA12{slash}M4_Dir") (class "Default")
      (node (ref "U11") (pin "33") (pinfunction "PA12_33") (pintype "passive"))
      (node (ref "U5") (pin "2") (pinfunction "IN2_2") (pintype "passive"))
    )
    (net (code "26") (name "/PA13{slash}SWDIO") (class "Default")
      (node (ref "R11") (pin "1") (pinfunction "1_1") (pintype "passive"))
      (node (ref "SWD") (pin "2") (pinfunction "2_2") (pintype "passive"))
      (node (ref "U11") (pin "34") (pinfunction "PA13_34") (pintype "passive"))
    )
    (net (code "27") (name "/PA14{slash}SWCLK") (class "Default")
      (node (ref "R10") (pin "1") (pinfunction "1_1") (pintype "passive"))
      (node (ref "SWD") (pin "3") (pinfunction "3_3") (pintype "passive"))
      (node (ref "U11") (pin "37") (pinfunction "PA14_37") (pintype "passive"))
    )
    (net (code "28") (name "/PA15{slash}TIMER1_CH0") (class "Default")
      (node (ref "CN3") (pin "3") (pinfunction "3_3") (pintype "passive"))
      (node (ref "U11") (pin "38") (pinfunction "PA15_38") (pintype "passive"))
    )
    (net (code "29") (name "/PB0{slash}LED0") (class "Default")
      (node (ref "CN2") (pin "4") (pinfunction "4_4") (pintype "passive"))
      (node (ref "R16") (pin "2") (pinfunction "2_2") (pintype "passive"))
      (node (ref "U11") (pin "18") (pinfunction "PB0_18") (pintype "passive"))
    )
    (net (code "30") (name "/PB1{slash}LED1") (class "Default")
      (node (ref "CN2") (pin "3") (pinfunction "3_3") (pintype "passive"))
      (node (ref "R17") (pin "2") (pinfunction "2_2") (pintype "passive"))
      (node (ref "U11") (pin "19") (pinfunction "PB1_19") (pintype "passive"))
    )
    (net (code "31") (name "/PB2") (class "Default")
      (node (ref "CN2") (pin "2") (pinfunction "2_2") (pintype "passive"))
      (node (ref "U11") (pin "20") (pinfunction "PB2_20") (pintype "passive"))
    )
    (net (code "32") (name "/PB3{slash}TIMER1_CH1") (class "Default")
      (node (ref "CN3") (pin "4") (pinfunction "4_4") (pintype "passive"))
      (node (ref "U11") (pin "39") (pinfunction "PB3_39") (pintype "passive"))
    )
    (net (code "33") (name "/PB4{slash}TIMER2_CH0") (class "Default")
      (node (ref "CN4") (pin "3") (pinfunction "3_3") (pintype "passive"))
      (node (ref "U11") (pin "40") (pinfunction "PB4_40") (pintype "passive"))
    )
    (net (code "34") (name "/PB5{slash}TIMER2_CH1") (class "Default")
      (node (ref "CN4") (pin "4") (pinfunction "4_4") (pintype "passive"))
      (node (ref "U11") (pin "41") (pinfunction "PB5_41") (pintype "passive"))
    )
    (net (code "35") (name "/PB6{slash}USART0_TX") (class "Default")
      (node (ref "CN8") (pin "2") (pinfunction "2_2") (pintype "passive"))
      (node (ref "U11") (pin "42") (pinfunction "PB6_42") (pintype "passive"))
    )
    (net (code "36") (name "/PB7{slash}USART0_RX") (class "Default")
      (node (ref "CN8") (pin "3") (pinfunction "3_3") (pintype "passive"))
      (node (ref "U11") (pin "43") (pinfunction "PB7_43") (pintype "passive"))
    )
    (net (code "37") (name "/PB8{slash}M4_Dir") (class "Default")
      (node (ref "U10") (pin "2") (pinfunction "IN2_2") (pintype "passive"))
      (node (ref "U11") (pin "45") (pinfunction "PB8_45") (pintype "passive"))
    )
    (net (code "38") (name "/PB9{slash}M2_Dir") (class "Default")
      (node (ref "U11") (pin "46") (pinfunction "PB9_46") (pintype "passive"))
      (node (ref "U4") (pin "2") (pinfunction "IN2_2") (pintype "passive"))
    )
    (net (code "39") (name "/PB10{slash}USART2_TX") (class "Default")
      (node (ref "U11") (pin "21") (pinfunction "PB10_21") (pintype "passive"))
      (node (ref "U12") (pin "11") (pinfunction "TXIN1_11") (pintype "passive"))
    )
    (net (code "40") (name "/PB11{slash}USART2_RX") (class "Default")
      (node (ref "U11") (pin "22") (pinfunction "PB11_22") (pintype "passive"))
      (node (ref "U12") (pin "12") (pinfunction "RXOUT1#_12") (pintype "passive"))
    )
    (net (code "41") (name "/PB12{slash}M1_Dir") (class "Default")
      (node (ref "U11") (pin "25") (pinfunction "PB12_25") (pintype "passive"))
      (node (ref "U3") (pin "2") (pinfunction "IN2_2") (pintype "passive"))
    )
    (net (code "42") (name "/PB13{slash}KEY0") (class "Default")
      (node (ref "CN2") (pin "1") (pinfunction "1_1") (pintype "passive"))
      (node (ref "KEY0") (pin "2") (pinfunction "2_2") (pintype "passive"))
      (node (ref "U11") (pin "26") (pinfunction "PB13_26") (pintype "passive"))
    )
    (net (code "43") (name "/PB14{slash}TIMER11_CH0") (class "Default")
      (node (ref "CN6") (pin "3") (pinfunction "3_3") (pintype "passive"))
      (node (ref "U11") (pin "27") (pinfunction "PB14_27") (pintype "passive"))
    )
    (net (code "44") (name "/PB15{slash}TIMER11_CH1") (class "Default")
      (node (ref "CN6") (pin "4") (pinfunction "4_4") (pintype "passive"))
      (node (ref "U11") (pin "28") (pinfunction "PB15_28") (pintype "passive"))
    )
    (net (code "45") (name "/RX") (class "Default")
      (node (ref "CN10") (pin "2") (pinfunction "2_2") (pintype "passive"))
      (node (ref "U12") (pin "13") (pinfunction "RXIN1_13") (pintype "passive"))
    )
    (net (code "46") (name "/TX") (class "Default")
      (node (ref "CN10") (pin "3") (pinfunction "3_3") (pintype "passive"))
      (node (ref "U12") (pin "14") (pinfunction "TXOUT1#_14") (pintype "passive"))
    )
    (net (code "47") (name "/VIN") (class "Default")
      (node (ref "DC1") (pin "1") (pinfunction "1_1") (pintype "passive"))
      (node (ref "P1") (pin "1") (pinfunction "1_1") (pintype "passive"))
      (node (ref "SW1") (pin "2") (pinfunction "2_2") (pintype "passive"))
    )
    (net (code "48") (name "3V3") (class "Default")
      (node (ref "C16") (pin "1") (pinfunction "1_1") (pintype "passive"))
      (node (ref "C17") (pin "1") (pinfunction "1_1") (pintype "passive"))
      (node (ref "C21") (pin "2") (pinfunction "2_2") (pintype "passive"))
      (node (ref "C23") (pin "2") (pinfunction "2_2") (pintype "passive"))
      (node (ref "C24") (pin "2") (pinfunction "2_2") (pintype "passive"))
      (node (ref "C25") (pin "2") (pinfunction "2_2") (pintype "passive"))
      (node (ref "C26") (pin "2") (pinfunction "2_2") (pintype "passive"))
      (node (ref "C33") (pin "2") (pinfunction "2_2") (pintype "passive"))
      (node (ref "C36") (pin "2") (pinfunction "2_2") (pintype "passive"))
      (node (ref "C37") (pin "1") (pinfunction "1_1") (pintype "passive"))
      (node (ref "C4") (pin "2") (pinfunction "2_2") (pintype "passive"))
      (node (ref "CN1") (pin "5") (pinfunction "5_5") (pintype "passive"))
      (node (ref "CN1") (pin "6") (pinfunction "6_6") (pintype "passive"))
      (node (ref "R11") (pin "2") (pinfunction "2_2") (pintype "passive"))
      (node (ref "R14") (pin "2") (pinfunction "2_2") (pintype "passive"))
      (node (ref "R18") (pin "1") (pinfunction "1_1") (pintype "passive"))
      (node (ref "R19") (pin "1") (pinfunction "1_1") (pintype "passive"))
      (node (ref "R9") (pin "2") (pinfunction "2_2") (pintype "passive"))
      (node (ref "U1") (pin "2") (pinfunction "VOUT_2") (pintype "passive"))
      (node (ref "U11") (pin "1") (pinfunction "VBAT_1") (pintype "passive"))
      (node (ref "U11") (pin "24") (pinfunction "VDD_1_24") (pintype "passive"))
      (node (ref "U11") (pin "36") (pinfunction "VDD_2_36") (pintype "passive"))
      (node (ref "U11") (pin "48") (pinfunction "VDD_3_48") (pintype "passive"))
      (node (ref "U11") (pin "9") (pinfunction "VDDA_9") (pintype "passive"))
      (node (ref "U12") (pin "16") (pinfunction "VCC_16") (pintype "passive"))
      (node (ref "U13") (pin "13") (pinfunction "VDD_13") (pintype "passive"))
      (node (ref "U13") (pin "8") (pinfunction "VLOGIC_8") (pintype "passive"))
      (node (ref "U15") (pin "13") (pinfunction "VDDIO_13") (pintype "passive"))
      (node (ref "U15") (pin "2") (pinfunction "VDD_2") (pintype "passive"))
      (node (ref "U15") (pin "4") (pinfunction "S1_4") (pintype "passive"))
    )
    (net (code "49") (name "AGND") (class "Default")
      (node (ref "C10") (pin "2") (pinfunction "2_2") (pintype "passive"))
      (node (ref "C11") (pin "2") (pinfunction "2_2") (pintype "passive"))
      (node (ref "C12") (pin "1") (pinfunction "1_1") (pintype "passive"))
      (node (ref "C13") (pin "1") (pinfunction "1_1") (pintype "passive"))
      (node (ref "C14") (pin "2") (pinfunction "2_2") (pintype "passive"))
      (node (ref "C15") (pin "2") (pinfunction "2_2") (pintype "passive"))
      (node (ref "C5") (pin "1") (pinfunction "1_1") (pintype "passive"))
      (node (ref "C6") (pin "1") (pinfunction "1_1") (pintype "passive"))
      (node (ref "C7") (pin "2") (pinfunction "2_2") (pintype "passive"))
      (node (ref "C8") (pin "2") (pinfunction "2_2") (pintype "passive"))
      (node (ref "C9") (pin "2") (pinfunction "2_2") (pintype "passive"))
      (node (ref "D1") (pin "2") (pinfunction "2_2") (pintype "passive"))
      (node (ref "DC1") (pin "3") (pinfunction "3_3") (pintype "passive"))
      (node (ref "P1") (pin "2") (pinfunction "2_2") (pintype "passive"))
      (node (ref "P2") (pin "2") (pinfunction "2_2") (pintype "passive"))
      (node (ref "R1") (pin "1") (pinfunction "1_1") (pintype "passive"))
      (node (ref "R3") (pin "1") (pinfunction "1_1") (pintype "passive"))
      (node (ref "R4") (pin "1") (pinfunction "1_1") (pintype "passive"))
      (node (ref "R5") (pin "1") (pinfunction "1_1") (pintype "passive"))
      (node (ref "R6") (pin "1") (pinfunction "1_1") (pintype "passive"))
      (node (ref "R7") (pin "1") (pinfunction "1_1") (pintype "passive"))
      (node (ref "U10") (pin "1") (pinfunction "GND_1") (pintype "passive"))
      (node (ref "U10") (pin "9") (pinfunction "EP_9") (pintype "passive"))
      (node (ref "U2") (pin "1") (pinfunction "GND_1") (pintype "passive"))
      (node (ref "U3") (pin "1") (pinfunction "GND_1") (pintype "passive"))
      (node (ref "U3") (pin "9") (pinfunction "EP_9") (pintype "passive"))
      (node (ref "U4") (pin "1") (pinfunction "GND_1") (pintype "passive"))
      (node (ref "U4") (pin "9") (pinfunction "EP_9") (pintype "passive"))
      (node (ref "U5") (pin "1") (pinfunction "GND_1") (pintype "passive"))
      (node (ref "U5") (pin "9") (pinfunction "EP_9") (pintype "passive"))
      (node (ref "Vin") (pin "2") (pinfunction "C_2") (pintype "passive"))
    )
    (net (code "50") (name "DGND") (class "Default")
      (node (ref "3V3") (pin "2") (pinfunction "C_2") (pintype "passive"))
      (node (ref "5V") (pin "2") (pinfunction "C_2") (pintype "passive"))
      (node (ref "C1") (pin "2") (pinfunction "2_2") (pintype "passive"))
      (node (ref "C16") (pin "2") (pinfunction "2_2") (pintype "passive"))
      (node (ref "C17") (pin "2") (pinfunction "2_2") (pintype "passive"))
      (node (ref "C18") (pin "1") (pinfunction "1_1") (pintype "passive"))
      (node (ref "C19") (pin "1") (pinfunction "1_1") (pintype "passive"))
      (node (ref "C2") (pin "2") (pinfunction "2_2") (pintype "passive"))
      (node (ref "C21") (pin "1") (pinfunction "1_1") (pintype "passive"))
      (node (ref "C22") (pin "1") (pinfunction "1_1") (pintype "passive"))
      (node (ref "C23") (pin "1") (pinfunction "1_1") (pintype "passive"))
      (node (ref "C24") (pin "1") (pinfunction "1_1") (pintype "passive"))
      (node (ref "C25") (pin "1") (pinfunction "1_1") (pintype "passive"))
      (node (ref "C26") (pin "1") (pinfunction "1_1") (pintype "passive"))
      (node (ref "C28") (pin "1") (pinfunction "1_1") (pintype "passive"))
      (node (ref "C29") (pin "2") (pinfunction "2_2") (pintype "passive"))
      (node (ref "C30") (pin "2") (pinfunction "2_2") (pintype "passive"))
      (node (ref "C31") (pin "2") (pinfunction "2_2") (pintype "passive"))
      (node (ref "C32") (pin "2") (pinfunction "2_2") (pintype "passive"))
      (node (ref "C33") (pin "1") (pinfunction "1_1") (pintype "passive"))
      (node (ref "C34") (pin "2") (pinfunction "2_2") (pintype "passive"))
      (node (ref "C35") (pin "1") (pinfunction "1_1") (pintype "passive"))
      (node (ref "C36") (pin "1") (pinfunction "1_1") (pintype "passive"))
      (node (ref "C37") (pin "2") (pinfunction "2_2") (pintype "passive"))
      (node (ref "C38") (pin "1") (pinfunction "1_1") (pintype "passive"))
      (node (ref "C39") (pin "2") (pinfunction "2_2") (pintype "passive"))
      (node (ref "C4") (pin "1") (pinfunction "1_1") (pintype "passive"))
      (node (ref "CN1") (pin "3") (pinfunction "3_3") (pintype "passive"))
      (node (ref "CN1") (pin "4") (pinfunction "4_4") (pintype "passive"))
      (node (ref "CN10") (pin "4") (pinfunction "4_4") (pintype "passive"))
      (node (ref "CN3") (pin "2") (pinfunction "2_2") (pintype "passive"))
      (node (ref "CN4") (pin "2") (pinfunction "2_2") (pintype "passive"))
      (node (ref "CN5") (pin "2") (pinfunction "2_2") (pintype "passive"))
      (node (ref "CN6") (pin "2") (pinfunction "2_2") (pintype "passive"))
      (node (ref "CN7") (pin "4") (pinfunction "4_4") (pintype "passive"))
      (node (ref "CN8") (pin "4") (pinfunction "4_4") (pintype "passive"))
      (node (ref "KEY0") (pin "1") (pinfunction "1_1") (pintype "passive"))
      (node (ref "LED0") (pin "2") (pinfunction "C_2") (pintype "passive"))
      (node (ref "LED1") (pin "2") (pinfunction "C_2") (pintype "passive"))
      (node (ref "R1") (pin "2") (pinfunction "2_2") (pintype "passive"))
      (node (ref "R10") (pin "2") (pinfunction "2_2") (pintype "passive"))
      (node (ref "R8") (pin "2") (pinfunction "2_2") (pintype "passive"))
      (node (ref "RESET") (pin "1") (pinfunction "1_1") (pintype "passive"))
      (node (ref "SWD") (pin "4") (pinfunction "4_4") (pintype "passive"))
      (node (ref "U1") (pin "1") (pinfunction "ADJ/GND_1") (pintype "passive"))
      (node (ref "U1") (pin "4") (pinfunction "VOUT_4") (pintype "passive"))
      (node (ref "U11") (pin "23") (pinfunction "VSS_1_23") (pintype "passive"))
      (node (ref "U11") (pin "35") (pinfunction "VSS_2_35") (pintype "passive"))
      (node (ref "U11") (pin "47") (pinfunction "VSS_3_47") (pintype "passive"))
      (node (ref "U11") (pin "8") (pinfunction "VSSA_8") (pintype "passive"))
      (node (ref "U12") (pin "15") (pinfunction "GND_15") (pintype "passive"))
      (node (ref "U13") (pin "1") (pinfunction "CLKIN_1") (pintype "passive"))
      (node (ref "U13") (pin "11") (pinfunction "FSYNC_11") (pintype "passive"))
      (node (ref "U13") (pin "18") (pinfunction "GND_18") (pintype "passive"))
      (node (ref "U13") (pin "9") (pinfunction "AD0_9") (pintype "passive"))
      (node (ref "U14") (pin "1") (pinfunction "GND_1") (pintype "passive"))
      (node (ref "U15") (pin "11") (pinfunction "GND_11") (pintype "passive"))
      (node (ref "U15") (pin "9") (pinfunction "GND_9") (pintype "passive"))
      (node (ref "USB1") (pin "4") (pinfunction "ID_4") (pintype "passive"))
      (node (ref "USB1") (pin "5") (pinfunction "GND_5") (pintype "passive"))
      (node (ref "USB1") (pin "6") (pinfunction "6_6") (pintype "passive"))
      (node (ref "X2") (pin "2") (pinfunction "GND_2") (pintype "passive"))
      (node (ref "X2") (pin "4") (pinfunction "GND_4") (pintype "passive"))
    )
    (net (code "51") (name "Net-(3V3-A)") (class "Default")
      (node (ref "3V3") (pin "1") (pinfunction "A_1") (pintype "passive"))
      (node (ref "R14") (pin "1") (pinfunction "1_1") (pintype "passive"))
    )
    (net (code "52") (name "Net-(5V-A)") (class "Default")
      (node (ref "5V") (pin "1") (pinfunction "A_1") (pintype "passive"))
      (node (ref "R13") (pin "1") (pinfunction "1_1") (pintype "passive"))
    )
    (net (code "53") (name "Net-(D1-Pad1)") (class "Default")
      (node (ref "D1") (pin "1") (pinfunction "1_1") (pintype "passive"))
      (node (ref "L1") (pin "2") (pinfunction "2_2") (pintype "passive"))
      (node (ref "U2") (pin "3") (pinfunction "SW_3") (pintype "passive"))
      (node (ref "U2") (pin "6") (pinfunction "SW_6") (pintype "passive"))
    )
    (net (code "54") (name "Net-(LED0-A)") (class "Default")
      (node (ref "LED0") (pin "1") (pinfunction "A_1") (pintype "passive"))
      (node (ref "R16") (pin "1") (pinfunction "1_1") (pintype "passive"))
    )
    (net (code "55") (name "Net-(LED1-A)") (class "Default")
      (node (ref "LED1") (pin "1") (pinfunction "A_1") (pintype "passive"))
      (node (ref "R17") (pin "1") (pinfunction "1_1") (pintype "passive"))
    )
    (net (code "56") (name "Net-(U2-FB)") (class "Default")
      (node (ref "C3") (pin "1") (pinfunction "1_1") (pintype "passive"))
      (node (ref "R2") (pin "2") (pinfunction "2_2") (pintype "passive"))
      (node (ref "R5") (pin "2") (pinfunction "2_2") (pintype "passive"))
      (node (ref "U2") (pin "2") (pinfunction "FB_2") (pintype "passive"))
    )
    (net (code "57") (name "Net-(U3-LSS)") (class "Default")
      (node (ref "R3") (pin "2") (pinfunction "2_2") (pintype "passive"))
      (node (ref "U3") (pin "7") (pinfunction "LSS_7") (pintype "passive"))
    )
    (net (code "58") (name "Net-(U4-LSS)") (class "Default")
      (node (ref "R4") (pin "2") (pinfunction "2_2") (pintype "passive"))
      (node (ref "U4") (pin "7") (pinfunction "LSS_7") (pintype "passive"))
    )
    (net (code "59") (name "Net-(U5-LSS)") (class "Default")
      (node (ref "R6") (pin "2") (pinfunction "2_2") (pintype "passive"))
      (node (ref "U5") (pin "7") (pinfunction "LSS_7") (pintype "passive"))
    )
    (net (code "60") (name "Net-(U10-LSS)") (class "Default")
      (node (ref "R7") (pin "2") (pinfunction "2_2") (pintype "passive"))
      (node (ref "U10") (pin "7") (pinfunction "LSS_7") (pintype "passive"))
    )
    (net (code "61") (name "Net-(U11-BOOT0)") (class "Default")
      (node (ref "R8") (pin "1") (pinfunction "1_1") (pintype "passive"))
      (node (ref "U11") (pin "44") (pinfunction "BOOT0_44") (pintype "passive"))
    )
    (net (code "62") (name "Net-(U11-NRST)") (class "Default")
      (node (ref "C18") (pin "2") (pinfunction "2_2") (pintype "passive"))
      (node (ref "R9") (pin "1") (pinfunction "1_1") (pintype "passive"))
      (node (ref "RESET") (pin "2") (pinfunction "2_2") (pintype "passive"))
      (node (ref "U11") (pin "7") (pinfunction "NRST_7") (pintype "passive"))
    )
    (net (code "63") (name "Net-(U12-C1+)") (class "Default")
      (node (ref "C20") (pin "1") (pinfunction "1_1") (pintype "passive"))
      (node (ref "U12") (pin "1") (pinfunction "C1+_1") (pintype "passive"))
    )
    (net (code "64") (name "Net-(U12-C1-)") (class "Default")
      (node (ref "C20") (pin "2") (pinfunction "2_2") (pintype "passive"))
      (node (ref "U12") (pin "3") (pinfunction "C1-_3") (pintype "passive"))
    )
    (net (code "65") (name "Net-(U12-C2+)") (class "Default")
      (node (ref "C27") (pin "1") (pinfunction "1_1") (pintype "passive"))
      (node (ref "U12") (pin "4") (pinfunction "C2+_4") (pintype "passive"))
    )
    (net (code "66") (name "Net-(U12-C2-)") (class "Default")
      (node (ref "C27") (pin "2") (pinfunction "2_2") (pintype "passive"))
      (node (ref "U12") (pin "5") (pinfunction "C2-_5") (pintype "passive"))
    )
    (net (code "67") (name "Net-(U12-V+)") (class "Default")
      (node (ref "C19") (pin "2") (pinfunction "2_2") (pintype "passive"))
      (node (ref "U12") (pin "2") (pinfunction "V+_2") (pintype "passive"))
    )
    (net (code "68") (name "Net-(U12-V-)") (class "Default")
      (node (ref "C29") (pin "1") (pinfunction "1_1") (pintype "passive"))
      (node (ref "U12") (pin "6") (pinfunction "V-_6") (pintype "passive"))
    )
    (net (code "69") (name "Net-(U13-CPOUT)") (class "Default")
      (node (ref "C32") (pin "1") (pinfunction "1_1") (pintype "passive"))
      (node (ref "U13") (pin "20") (pinfunction "CPOUT_20") (pintype "passive"))
    )
    (net (code "70") (name "Net-(U13-REGOUT)") (class "Default")
      (node (ref "C35") (pin "2") (pinfunction "2_2") (pintype "passive"))
      (node (ref "U13") (pin "10") (pinfunction "REGOUT_10") (pintype "passive"))
    )
    (net (code "71") (name "Net-(U14-V3)") (class "Default")
      (node (ref "C31") (pin "1") (pinfunction "1_1") (pintype "passive"))
      (node (ref "U14") (pin "4") (pinfunction "V3_4") (pintype "passive"))
    )
    (net (code "72") (name "Net-(U14-VCC)") (class "Default")
      (node (ref "C30") (pin "1") (pinfunction "1_1") (pintype "passive"))
      (node (ref "U14") (pin "16") (pinfunction "VCC_16") (pintype "passive"))
    )
    (net (code "73") (name "Net-(U14-XI)") (class "Default")
      (node (ref "C38") (pin "2") (pinfunction "2_2") (pintype "passive"))
      (node (ref "U14") (pin "7") (pinfunction "XI_7") (pintype "passive"))
      (node (ref "X2") (pin "3") (pinfunction "OSC2_3") (pintype "passive"))
    )
    (net (code "74") (name "Net-(U14-XO)") (class "Default")
      (node (ref "C39") (pin "1") (pinfunction "1_1") (pintype "passive"))
      (node (ref "U14") (pin "8") (pinfunction "XO_8") (pintype "passive"))
      (node (ref "X2") (pin "1") (pinfunction "OSC1_1") (pintype "passive"))
    )
    (net (code "75") (name "Net-(U15-C1)") (class "Default")
      (node (ref "C34") (pin "1") (pinfunction "1_1") (pintype "passive"))
      (node (ref "U15") (pin "10") (pinfunction "C1_10") (pintype "passive"))
    )
    (net (code "76") (name "Net-(U15-SETC)") (class "Default")
      (node (ref "C40") (pin "2") (pinfunction "2_2") (pintype "passive"))
      (node (ref "U15") (pin "12") (pinfunction "SETC_12") (pintype "passive"))
    )
    (net (code "77") (name "Net-(U15-SETP)") (class "Default")
      (node (ref "C40") (pin "1") (pinfunction "1_1") (pintype "passive"))
      (node (ref "U15") (pin "8") (pinfunction "SETP_8") (pintype "passive"))
    )
    (net (code "78") (name "Net-(Vin-A)") (class "Default")
      (node (ref "R12") (pin "1") (pinfunction "1_1") (pintype "passive"))
      (node (ref "Vin") (pin "1") (pinfunction "A_1") (pintype "passive"))
    )
    (net (code "79") (name "VIN_OPEN") (class "Default")
      (node (ref "C10") (pin "1") (pinfunction "1_1") (pintype "passive"))
      (node (ref "C12") (pin "2") (pinfunction "2_2") (pintype "passive"))
      (node (ref "C13") (pin "2") (pinfunction "2_2") (pintype "passive"))
      (node (ref "C14") (pin "1") (pinfunction "1_1") (pintype "passive"))
      (node (ref "C15") (pin "1") (pinfunction "1_1") (pintype "passive"))
      (node (ref "C5") (pin "2") (pinfunction "2_2") (pintype "passive"))
      (node (ref "C6") (pin "2") (pinfunction "2_2") (pintype "passive"))
      (node (ref "C7") (pin "1") (pinfunction "1_1") (pintype "passive"))
      (node (ref "C8") (pin "1") (pinfunction "1_1") (pintype "passive"))
      (node (ref "C9") (pin "1") (pinfunction "1_1") (pintype "passive"))
      (node (ref "R12") (pin "2") (pinfunction "2_2") (pintype "passive"))
      (node (ref "SW1") (pin "1") (pinfunction "1_1") (pintype "passive"))
      (node (ref "U10") (pin "5") (pinfunction "VBB_5") (pintype "passive"))
      (node (ref "U2") (pin "4") (pinfunction "EN_4") (pintype "passive"))
      (node (ref "U2") (pin "5") (pinfunction "VIN_5") (pintype "passive"))
      (node (ref "U3") (pin "5") (pinfunction "VBB_5") (pintype "passive"))
      (node (ref "U4") (pin "5") (pinfunction "VBB_5") (pintype "passive"))
      (node (ref "U5") (pin "5") (pinfunction "VBB_5") (pintype "passive"))
    )
    (net (code "80") (name "VOUT_5V{slash}5A") (class "Default")
      (node (ref "C1") (pin "1") (pinfunction "1_1") (pintype "passive"))
      (node (ref "C11") (pin "1") (pinfunction "1_1") (pintype "passive"))
      (node (ref "C2") (pin "1") (pinfunction "1_1") (pintype "passive"))
      (node (ref "C3") (pin "2") (pinfunction "2_2") (pintype "passive"))
      (node (ref "CN1") (pin "1") (pinfunction "1_1") (pintype "passive"))
      (node (ref "CN1") (pin "2") (pinfunction "2_2") (pintype "passive"))
      (node (ref "CN10") (pin "1") (pinfunction "1_1") (pintype "passive"))
      (node (ref "CN3") (pin "5") (pinfunction "5_5") (pintype "passive"))
      (node (ref "CN4") (pin "5") (pinfunction "5_5") (pintype "passive"))
      (node (ref "CN5") (pin "5") (pinfunction "5_5") (pintype "passive"))
      (node (ref "CN6") (pin "5") (pinfunction "5_5") (pintype "passive"))
      (node (ref "CN7") (pin "1") (pinfunction "1_1") (pintype "passive"))
      (node (ref "CN8") (pin "1") (pinfunction "1_1") (pintype "passive"))
      (node (ref "L1") (pin "1") (pinfunction "1_1") (pintype "passive"))
      (node (ref "P2") (pin "1") (pinfunction "1_1") (pintype "passive"))
      (node (ref "R13") (pin "2") (pinfunction "2_2") (pintype "passive"))
      (node (ref "R2") (pin "1") (pinfunction "1_1") (pintype "passive"))
      (node (ref "SWD") (pin "1") (pinfunction "1_1") (pintype "passive"))
      (node (ref "U1") (pin "3") (pinfunction "VIN_3") (pintype "passive"))
      (node (ref "U10") (pin "4") (pinfunction "VREF_4") (pintype "passive"))
      (node (ref "U3") (pin "4") (pinfunction "VREF_4") (pintype "passive"))
      (node (ref "U4") (pin "4") (pinfunction "VREF_4") (pintype "passive"))
      (node (ref "U5") (pin "4") (pinfunction "VREF_4") (pintype "passive"))
    )
    (net (code "81") (name "unconnected-(DC1-Pad2)") (class "Default")
      (node (ref "DC1") (pin "2") (pinfunction "2_2") (pintype "passive+no_connect"))
    )
    (net (code "82") (name "unconnected-(SW1-Pad3)") (class "Default")
      (node (ref "SW1") (pin "3") (pinfunction "3_3") (pintype "passive+no_connect"))
    )
    (net (code "83") (name "unconnected-(U6-Pad1)") (class "Default")
      (node (ref "U6") (pin "1") (pinfunction "1_1") (pintype "passive+no_connect"))
    )
    (net (code "84") (name "unconnected-(U7-Pad1)") (class "Default")
      (node (ref "U7") (pin "1") (pinfunction "1_1") (pintype "passive+no_connect"))
    )
    (net (code "85") (name "unconnected-(U8-Pad1)") (class "Default")
      (node (ref "U8") (pin "1") (pinfunction "1_1") (pintype "passive+no_connect"))
    )
    (net (code "86") (name "unconnected-(U9-Pad1)") (class "Default")
      (node (ref "U9") (pin "1") (pinfunction "1_1") (pintype "passive+no_connect"))
    )
    (net (code "87") (name "unconnected-(U11-PC13-TAMPER-RTC-Pad2)") (class "Default")
      (node (ref "U11") (pin "2") (pinfunction "PC13-TAMPER-RTC_2") (pintype "passive+no_connect"))
    )
    (net (code "88") (name "unconnected-(U11-PC14-OSC32_IN-Pad3)") (class "Default")
      (node (ref "U11") (pin "3") (pinfunction "PC14-OSC32_IN_3") (pintype "passive+no_connect"))
    )
    (net (code "89") (name "unconnected-(U11-PC15-OSC32_OUT-Pad4)") (class "Default")
      (node (ref "U11") (pin "4") (pinfunction "PC15-OSC32_OUT_4") (pintype "passive+no_connect"))
    )
    (net (code "90") (name "unconnected-(U12-RXIN2-Pad8)") (class "Default")
      (node (ref "U12") (pin "8") (pinfunction "RXIN2_8") (pintype "passive+no_connect"))
    )
    (net (code "91") (name "unconnected-(U12-RXOUT2#-Pad9)") (class "Default")
      (node (ref "U12") (pin "9") (pinfunction "RXOUT2#_9") (pintype "passive+no_connect"))
    )
    (net (code "92") (name "unconnected-(U12-TXIN2-Pad10)") (class "Default")
      (node (ref "U12") (pin "10") (pinfunction "TXIN2_10") (pintype "passive+no_connect"))
    )
    (net (code "93") (name "unconnected-(U12-TXOUT2#-Pad7)") (class "Default")
      (node (ref "U12") (pin "7") (pinfunction "TXOUT2#_7") (pintype "passive+no_connect"))
    )
    (net (code "94") (name "unconnected-(U13-AUX_CL-Pad7)") (class "Default")
      (node (ref "U13") (pin "7") (pinfunction "AUX_CL_7") (pintype "passive+no_connect"))
    )
    (net (code "95") (name "unconnected-(U13-AUX_DA-Pad6)") (class "Default")
      (node (ref "U13") (pin "6") (pinfunction "AUX_DA_6") (pintype "passive+no_connect"))
    )
    (net (code "96") (name "unconnected-(U13-EP-Pad25)") (class "Default")
      (node (ref "U13") (pin "25") (pinfunction "EP_25") (pintype "passive+no_connect"))
    )
    (net (code "97") (name "unconnected-(U13-NC-Pad2)") (class "Default")
      (node (ref "U13") (pin "2") (pinfunction "NC_2") (pintype "passive+no_connect"))
    )
    (net (code "98") (name "unconnected-(U13-NC-Pad3)") (class "Default")
      (node (ref "U13") (pin "3") (pinfunction "NC_3") (pintype "passive+no_connect"))
    )
    (net (code "99") (name "unconnected-(U13-NC-Pad4)") (class "Default")
      (node (ref "U13") (pin "4") (pinfunction "NC_4") (pintype "passive+no_connect"))
    )
    (net (code "100") (name "unconnected-(U13-NC-Pad5)") (class "Default")
      (node (ref "U13") (pin "5") (pinfunction "NC_5") (pintype "passive+no_connect"))
    )
    (net (code "101") (name "unconnected-(U13-NC-Pad14)") (class "Default")
      (node (ref "U13") (pin "14") (pinfunction "NC_14") (pintype "passive+no_connect"))
    )
    (net (code "102") (name "unconnected-(U13-NC-Pad15)") (class "Default")
      (node (ref "U13") (pin "15") (pinfunction "NC_15") (pintype "passive+no_connect"))
    )
    (net (code "103") (name "unconnected-(U13-NC-Pad16)") (class "Default")
      (node (ref "U13") (pin "16") (pinfunction "NC_16") (pintype "passive+no_connect"))
    )
    (net (code "104") (name "unconnected-(U13-NC-Pad17)") (class "Default")
      (node (ref "U13") (pin "17") (pinfunction "NC_17") (pintype "passive+no_connect"))
    )
    (net (code "105") (name "unconnected-(U13-RESV-Pad19)") (class "Default")
      (node (ref "U13") (pin "19") (pinfunction "RESV_19") (pintype "passive+no_connect"))
    )
    (net (code "106") (name "unconnected-(U13-RESV-Pad21)") (class "Default")
      (node (ref "U13") (pin "21") (pinfunction "RESV_21") (pintype "passive+no_connect"))
    )
    (net (code "107") (name "unconnected-(U13-RESV-Pad22)") (class "Default")
      (node (ref "U13") (pin "22") (pinfunction "RESV_22") (pintype "passive+no_connect"))
    )
    (net (code "108") (name "unconnected-(U14-CTS#-Pad9)") (class "Default")
      (node (ref "U14") (pin "9") (pinfunction "CTS#_9") (pintype "passive+no_connect"))
    )
    (net (code "109") (name "unconnected-(U14-DCD#-Pad12)") (class "Default")
      (node (ref "U14") (pin "12") (pinfunction "DCD#_12") (pintype "passive+no_connect"))
    )
    (net (code "110") (name "unconnected-(U14-DSR#-Pad10)") (class "Default")
      (node (ref "U14") (pin "10") (pinfunction "DSR#_10") (pintype "passive+no_connect"))
    )
    (net (code "111") (name "unconnected-(U14-DTR#-Pad13)") (class "Default")
      (node (ref "U14") (pin "13") (pinfunction "DTR#_13") (pintype "passive+no_connect"))
    )
    (net (code "112") (name "unconnected-(U14-R232-Pad15)") (class "Default")
      (node (ref "U14") (pin "15") (pinfunction "R232_15") (pintype "passive+no_connect"))
    )
    (net (code "113") (name "unconnected-(U14-RI-Pad11)") (class "Default")
      (node (ref "U14") (pin "11") (pinfunction "RI_11") (pintype "passive+no_connect"))
    )
    (net (code "114") (name "unconnected-(U14-RTS#-Pad14)") (class "Default")
      (node (ref "U14") (pin "14") (pinfunction "RTS#_14") (pintype "passive+no_connect"))
    )
    (net (code "115") (name "unconnected-(U15-NC-Pad3)") (class "Default")
      (node (ref "U15") (pin "3") (pinfunction "NC_3") (pintype "passive+no_connect"))
    )
    (net (code "116") (name "unconnected-(U15-NC-Pad5)") (class "Default")
      (node (ref "U15") (pin "5") (pinfunction "NC_5") (pintype "passive+no_connect"))
    )
    (net (code "117") (name "unconnected-(U15-NC-Pad6)") (class "Default")
      (node (ref "U15") (pin "6") (pinfunction "NC_6") (pintype "passive+no_connect"))
    )
    (net (code "118") (name "unconnected-(U15-NC-Pad7)") (class "Default")
      (node (ref "U15") (pin "7") (pinfunction "NC_7") (pintype "passive+no_connect"))
    )
    (net (code "119") (name "unconnected-(U15-NC-Pad14)") (class "Default")
      (node (ref "U15") (pin "14") (pinfunction "NC_14") (pintype "passive+no_connect"))
    )
    (net (code "120") (name "unconnected-(USB1-VBUS-Pad1)") (class "Default")
      (node (ref "USB1") (pin "1") (pinfunction "VBUS_1") (pintype "passive"))
    )
  )
)
